# 5vadc.net
KiCad netlist of a schematic drawn in EAGLE
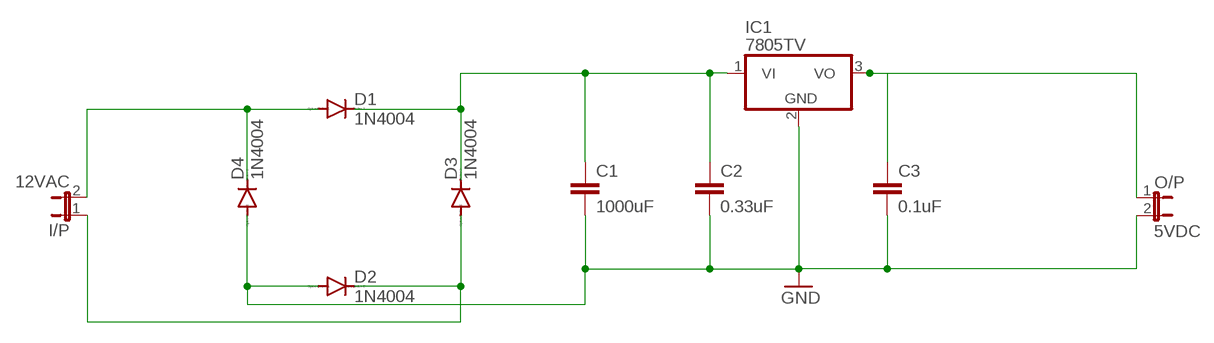
[diagram p0: schematic, sheet 1]

(export (version "E")
  (design (tool "Eeschema 10.0.6"))
  (components
    (comp (ref "C1")
      (value "1000uF")
      (footprint "eagle-import:C2.5-3")
      (libsource (lib "eagle-import") (part "C2,5-3"))
    )
    (comp (ref "C2")
      (value "0.33uF")
      (footprint "eagle-import:C2.5-3")
      (libsource (lib "eagle-import") (part "C2,5-3"))
    )
    (comp (ref "C3")
      (value "0.1uF")
      (footprint "eagle-import:C2.5-3")
      (libsource (lib "eagle-import") (part "C2,5-3"))
    )
    (comp (ref "D1")
      (value "1N4004")
      (footprint "eagle-import:DO41-10")
      (libsource (lib "eagle-import") (part "1N4004"))
    )
    (comp (ref "D2")
      (value "1N4004")
      (footprint "eagle-import:DO41-10")
      (libsource (lib "eagle-import") (part "1N4004"))
    )
    (comp (ref "D3")
      (value "1N4004")
      (footprint "eagle-import:DO41-10")
      (libsource (lib "eagle-import") (part "1N4004"))
    )
    (comp (ref "D4")
      (value "1N4004")
      (footprint "eagle-import:DO41-10")
      (libsource (lib "eagle-import") (part "1N4004"))
    )
    (comp (ref "I/P")
      (value "12VAC")
      (footprint "eagle-import:JP1")
      (libsource (lib "eagle-import") (part "JP1E"))
    )
    (comp (ref "IC1")
      (value "7805TV")
      (footprint "eagle-import:TO220V")
      (libsource (lib "eagle-import") (part "78TV05"))
    )
    (comp (ref "O/P")
      (value "5VDC")
      (footprint "eagle-import:JP1")
      (libsource (lib "eagle-import") (part "JP1E"))
    )
  )
  (nets
    (net (code "1") (name "GND") (class "Default")
      (node (ref "C1") (pin "2") (pinfunction "2_2") (pintype "passive"))
      (node (ref "C2") (pin "2") (pinfunction "2_2") (pintype "passive"))
      (node (ref "C3") (pin "2") (pinfunction "2_2") (pintype "passive"))
      (node (ref "D2") (pin "A") (pinfunction "A_A") (pintype "passive"))
      (node (ref "D4") (pin "A") (pinfunction "A_A") (pintype "passive"))
      (node (ref "IC1") (pin "2") (pinfunction "GND_2") (pintype "passive"))
      (node (ref "O/P") (pin "2") (pinfunction "2_2") (pintype "passive"))
    )
    (net (code "2") (name "Net-(D1-PadA)") (class "Default")
      (node (ref "D1") (pin "A") (pinfunction "A_A") (pintype "passive"))
      (node (ref "D4") (pin "C") (pinfunction "C_C") (pintype "passive"))
      (node (ref "I/P") (pin "2") (pinfunction "2_2") (pintype "passive"))
    )
    (net (code "3") (name "Net-(D2-PadC)") (class "Default")
      (node (ref "D2") (pin "C") (pinfunction "C_C") (pintype "passive"))
      (node (ref "D3") (pin "A") (pinfunction "A_A") (pintype "passive"))
      (node (ref "I/P") (pin "1") (pinfunction "1_1") (pintype "passive"))
    )
    (net (code "4") (name "Net-(IC1-VI)") (class "Default")
      (node (ref "C1") (pin "1") (pinfunction "1_1") (pintype "passive"))
      (node (ref "C2") (pin "1") (pinfunction "1_1") (pintype "passive"))
      (node (ref "D1") (pin "C") (pinfunction "C_C") (pintype "passive"))
      (node (ref "D3") (pin "C") (pinfunction "C_C") (pintype "passive"))
      (node (ref "IC1") (pin "1") (pinfunction "VI_1") (pintype "input"))
    )
    (net (code "5") (name "Net-(IC1-VO)") (class "Default")
      (node (ref "C3") (pin "1") (pinfunction "1_1") (pintype "passive"))
      (node (ref "IC1") (pin "3") (pinfunction "VO_3") (pintype "passive"))
      (node (ref "O/P") (pin "1") (pinfunction "1_1") (pintype "passive"))
    )
  )
)
